# sband.net
KiCad netlist of a schematic drawn in Altium Designer
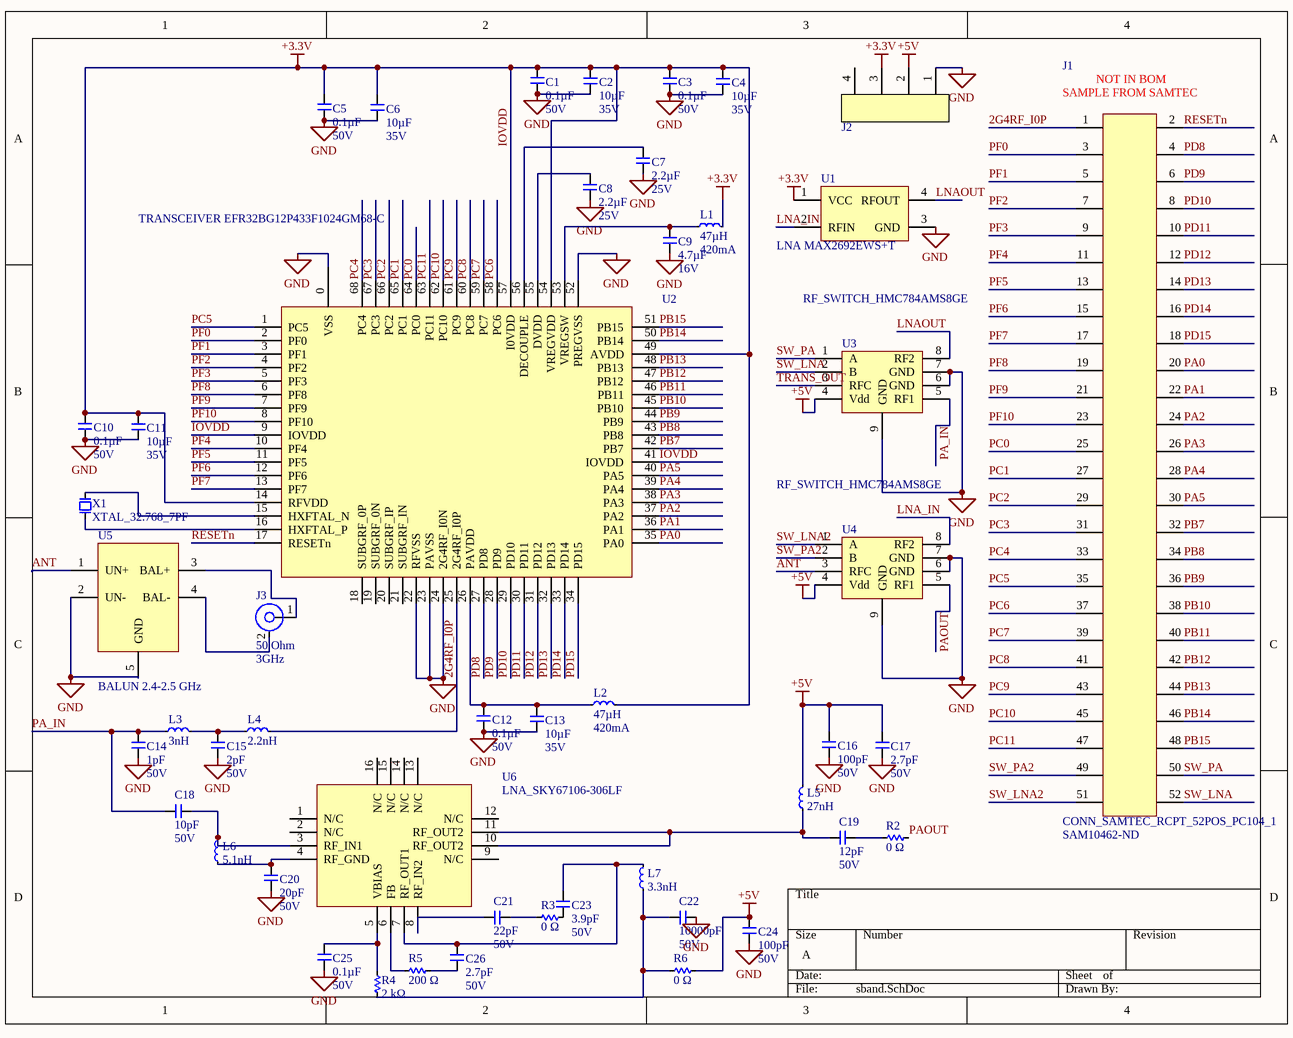
[diagram p0: sband.SchDoc]

(export (version "E")
  (design (tool "Eeschema 10.0.6"))
  (components
    (comp (ref "C1")
      (value "__template_cap")
      (footprint "C0603")
      (description "CAP CER 0603 0.1µF X7R 50V 10%")
      (fields
        (field (name "CAPACITANCE (SHORTHAND)") "0.1µF")
        (field (name "RATED VOLTAGE") "50V")
        (field (name "MANUFACTURER") "Murata Electronics North America")
      )
      (libsource (lib "passives") (part "__template_cap"))
    )
    (comp (ref "C2")
      (value "__template_cap")
      (footprint "C0603")
      (description "CAP CER 10UF 35V X5R 0603 20%")
      (fields
        (field (name "CAPACITANCE (SHORTHAND)") "10µF")
        (field (name "RATED VOLTAGE") "35V")
        (field (name "MANUFACTURER") "Murata Electronics North America")
      )
      (libsource (lib "passives") (part "__template_cap"))
    )
    (comp (ref "C3")
      (value "__template_cap")
      (footprint "C0603")
      (description "CAP CER 0603 0.1µF X7R 50V 10%")
      (fields
        (field (name "CAPACITANCE (SHORTHAND)") "0.1µF")
        (field (name "RATED VOLTAGE") "50V")
        (field (name "MANUFACTURER") "Murata Electronics North America")
      )
      (libsource (lib "passives") (part "__template_cap"))
    )
    (comp (ref "C4")
      (value "__template_cap")
      (footprint "C0603")
      (description "CAP CER 10UF 35V X5R 0603 20%")
      (fields
        (field (name "CAPACITANCE (SHORTHAND)") "10µF")
        (field (name "RATED VOLTAGE") "35V")
        (field (name "MANUFACTURER") "Murata Electronics North America")
      )
      (libsource (lib "passives") (part "__template_cap"))
    )
    (comp (ref "C5")
      (value "__template_cap")
      (footprint "C0603")
      (description "CAP CER 0603 0.1µF X7R 50V 10%")
      (fields
        (field (name "CAPACITANCE (SHORTHAND)") "0.1µF")
        (field (name "RATED VOLTAGE") "50V")
        (field (name "MANUFACTURER") "Murata Electronics North America")
      )
      (libsource (lib "passives") (part "__template_cap"))
    )
    (comp (ref "C6")
      (value "__template_cap")
      (footprint "C0603")
      (description "CAP CER 10UF 35V X5R 0603 20%")
      (fields
        (field (name "CAPACITANCE (SHORTHAND)") "10µF")
        (field (name "RATED VOLTAGE") "35V")
        (field (name "MANUFACTURER") "Murata Electronics North America")
      )
      (libsource (lib "passives") (part "__template_cap"))
    )
    (comp (ref "C7")
      (value "__template_cap")
      (footprint "C0603")
      (description "CAP CER 2.2UF 16V X5R 0603 10%")
      (fields
        (field (name "CAPACITANCE (SHORTHAND)") "2.2µF")
        (field (name "RATED VOLTAGE") "25V")
        (field (name "MANUFACTURER") "Murata Electronics North America")
      )
      (libsource (lib "passives") (part "__template_cap"))
    )
    (comp (ref "C8")
      (value "__template_cap")
      (footprint "C0603")
      (description "CAP CER 2.2UF 16V X5R 0603 10%")
      (fields
        (field (name "CAPACITANCE (SHORTHAND)") "2.2µF")
        (field (name "RATED VOLTAGE") "25V")
        (field (name "MANUFACTURER") "Murata Electronics North America")
      )
      (libsource (lib "passives") (part "__template_cap"))
    )
    (comp (ref "C9")
      (value "__template_cap")
      (footprint "C0603")
      (description "CAP CER 4.7UF 16V X5R 0603 10%")
      (fields
        (field (name "CAPACITANCE (SHORTHAND)") "4.7µF")
        (field (name "RATED VOLTAGE") "16V")
        (field (name "MANUFACTURER") "Yageo")
      )
      (libsource (lib "passives") (part "__template_cap"))
    )
    (comp (ref "C10")
      (value "__template_cap")
      (footprint "C0603")
      (description "CAP CER 0603 0.1µF X7R 50V 10%")
      (fields
        (field (name "CAPACITANCE (SHORTHAND)") "0.1µF")
        (field (name "RATED VOLTAGE") "50V")
        (field (name "MANUFACTURER") "Murata Electronics North America")
      )
      (libsource (lib "passives") (part "__template_cap"))
    )
    (comp (ref "C11")
      (value "__template_cap")
      (footprint "C0603")
      (description "CAP CER 10UF 35V X5R 0603 20%")
      (fields
        (field (name "CAPACITANCE (SHORTHAND)") "10µF")
        (field (name "RATED VOLTAGE") "35V")
        (field (name "MANUFACTURER") "Murata Electronics North America")
      )
      (libsource (lib "passives") (part "__template_cap"))
    )
    (comp (ref "C12")
      (value "__template_cap")
      (footprint "C0603")
      (description "CAP CER 0603 0.1µF X7R 50V 10%")
      (fields
        (field (name "CAPACITANCE (SHORTHAND)") "0.1µF")
        (field (name "RATED VOLTAGE") "50V")
        (field (name "MANUFACTURER") "Murata Electronics North America")
      )
      (libsource (lib "passives") (part "__template_cap"))
    )
    (comp (ref "C13")
      (value "__template_cap")
      (footprint "C0603")
      (description "CAP CER 10UF 35V X5R 0603 20%")
      (fields
        (field (name "CAPACITANCE (SHORTHAND)") "10µF")
        (field (name "RATED VOLTAGE") "35V")
        (field (name "MANUFACTURER") "Murata Electronics North America")
      )
      (libsource (lib "passives") (part "__template_cap"))
    )
    (comp (ref "C14")
      (value "__template_cap")
      (footprint "C0402")
      (description "CAP CER 1PF 50V C0G/NP0 0402")
      (fields
        (field (name "CAPACITANCE (SHORTHAND)") "1pF")
        (field (name "RATED VOLTAGE") "50V")
        (field (name "MANUFACTURER") "Murata Electronics North America")
        (field (name "TOLERANCE") "±0.1pF")
      )
      (libsource (lib "passives") (part "__template_cap"))
    )
    (comp (ref "C15")
      (value "__template_cap")
      (footprint "C0402")
      (description "CAP CER 2PF 50V C0G/NP0 0402")
      (fields
        (field (name "CAPACITANCE (SHORTHAND)") "2pF")
        (field (name "RATED VOLTAGE") "50V")
        (field (name "MANUFACTURER") "Murata Electronics North America")
        (field (name "TOLERANCE") "±0.1pF")
      )
      (libsource (lib "passives") (part "__template_cap"))
    )
    (comp (ref "C16")
      (value "__template_cap")
      (footprint "C0603")
      (description "CAP CER 100PF 50V C0G/NP0 0603")
      (fields
        (field (name "CAPACITANCE (SHORTHAND)") "100pF")
        (field (name "RATED VOLTAGE") "50V")
        (field (name "MANUFACTURER") "Murata Electronics North America")
      )
      (libsource (lib "passives") (part "__template_cap"))
    )
    (comp (ref "C17")
      (value "__template_cap")
      (footprint "C0402")
      (description "CAP CER 2.7PF 50V C0G/NP0 0402")
      (fields
        (field (name "CAPACITANCE (SHORTHAND)") "2.7pF")
        (field (name "RATED VOLTAGE") "50V")
        (field (name "MANUFACTURER") "Murata Electronics North America")
        (field (name "TOLERANCE") "±0.1pF")
      )
      (libsource (lib "passives") (part "__template_cap"))
    )
    (comp (ref "C18")
      (value "__template_cap")
      (footprint "C0402")
      (description "CAP CER 10PF 50V C0G/NP0 0402")
      (fields
        (field (name "CAPACITANCE (SHORTHAND)") "10pF")
        (field (name "RATED VOLTAGE") "50V")
        (field (name "MANUFACTURER") "Murata Electronics North America")
        (field (name "TOLERANCE") "±1%")
      )
      (libsource (lib "passives") (part "__template_cap"))
    )
    (comp (ref "C19")
      (value "__template_cap")
      (footprint "C0603")
      (description "CAP CER 12PF 50V C0G/NP0 0603")
      (fields
        (field (name "CAPACITANCE (SHORTHAND)") "12pF")
        (field (name "RATED VOLTAGE") "50V")
        (field (name "MANUFACTURER") "Murata Electronics North America")
      )
      (libsource (lib "passives") (part "__template_cap"))
    )
    (comp (ref "C20")
      (value "__template_cap")
      (footprint "C0402")
      (description "CAP CER 20PF 50V C0G/NP0 0402")
      (fields
        (field (name "CAPACITANCE (SHORTHAND)") "20pF")
        (field (name "RATED VOLTAGE") "50V")
        (field (name "MANUFACTURER") "Murata Electronics North America")
        (field (name "TOLERANCE") "±2%")
      )
      (libsource (lib "passives") (part "__template_cap"))
    )
    (comp (ref "C21")
      (value "__template_cap")
      (footprint "C0603")
      (description "CAP CER 22PF 50V C0G/NP0 0603")
      (fields
        (field (name "CAPACITANCE (SHORTHAND)") "22pF")
        (field (name "RATED VOLTAGE") "50V")
        (field (name "MANUFACTURER") "Murata Electronics North America")
      )
      (libsource (lib "passives") (part "__template_cap"))
    )
    (comp (ref "C22")
      (value "__template_cap")
      (footprint "C0603")
      (description "CAP CER 0603 10000pF X7R 50V 10%")
      (fields
        (field (name "CAPACITANCE (SHORTHAND)") "10000pF")
        (field (name "RATED VOLTAGE") "50V")
        (field (name "MANUFACTURER") "Murata Electronics North America")
      )
      (libsource (lib "passives") (part "__template_cap"))
    )
    (comp (ref "C23")
      (value "__template_cap")
      (footprint "C0402")
      (description "CAP CER 3.9PF 50V C0G/NP0 0402")
      (fields
        (field (name "CAPACITANCE (SHORTHAND)") "3.9pF")
        (field (name "RATED VOLTAGE") "50V")
        (field (name "MANUFACTURER") "Murata Electronics North America")
        (field (name "TOLERANCE") "±0.1pF")
      )
      (libsource (lib "passives") (part "__template_cap"))
    )
    (comp (ref "C24")
      (value "__template_cap")
      (footprint "C0603")
      (description "CAP CER 100PF 50V C0G/NP0 0603")
      (fields
        (field (name "CAPACITANCE (SHORTHAND)") "100pF")
        (field (name "RATED VOLTAGE") "50V")
        (field (name "MANUFACTURER") "Murata Electronics North America")
      )
      (libsource (lib "passives") (part "__template_cap"))
    )
    (comp (ref "C25")
      (value "__template_cap")
      (footprint "C0603")
      (description "CAP CER 0603 0.1µF X7R 50V 10%")
      (fields
        (field (name "CAPACITANCE (SHORTHAND)") "0.1µF")
        (field (name "RATED VOLTAGE") "50V")
        (field (name "MANUFACTURER") "Murata Electronics North America")
      )
      (libsource (lib "passives") (part "__template_cap"))
    )
    (comp (ref "C26")
      (value "__template_cap")
      (footprint "C0402")
      (description "CAP CER 2.7PF 50V C0G/NP0 0402")
      (fields
        (field (name "CAPACITANCE (SHORTHAND)") "2.7pF")
        (field (name "RATED VOLTAGE") "50V")
        (field (name "MANUFACTURER") "Murata Electronics North America")
        (field (name "TOLERANCE") "±0.1pF")
      )
      (libsource (lib "passives") (part "__template_cap"))
    )
    (comp (ref "J1")
      (value "CONN_SAMTEC_RCPT_52POS_PC104_1")
      (footprint "SAMTEC_ESQ-126-39-G-D")
      (description "CONN RCPT 52POS .100\" DUAL GOLD")
      (fields
        (field (name "MANUFACTURER") "Samtec Inc.")
        (field (name "MANUFACTURER PART NUMBER") "ESQ-126-39-G-D")
        (field (name "SUPPLIER PART NUMBER 1") "SAM10462-ND")
      )
      (libsource (lib "connector") (part "CONN_SAMTEC_RCPT_52POS_PC104_1"))
    )
    (comp (ref "J2")
      (value "CONN_1x4_MALE_SMD")
      (footprint "CONN_1x4_100MIL_MALE_SMD")
      (description "CONN HEADER 4POS MALE SMD")
      (fields
        (field (name "MANUFACTURER") "3M")
        (field (name "MANUFACTURER PART NUMBER") "961104-6700-AR-TP")
      )
      (libsource (lib "Stanford Student Space Initiative") (part "Symbol"))
    )
    (comp (ref "J3")
      (value "CONN_SMA_JACK_R/A_50_OHM_PCB")
      (footprint "TE_SMA_JACK_RA_5-1814400-1")
      (description "CONN SMA JACK R/A 50 OHM PCB")
      (fields
        (field (name "IMPEDANCE") "50 Ohm")
        (field (name "FREQUENCY - MAX") "3GHz")
        (field (name "MANUFACTURER") "TE Connectivity")
        (field (name "MANUFACTURER PART NUMBER") "5-1814400-1")
      )
      (libsource (lib "Stanford Student Space Initiative") (part "CONN_SMA_JACK_R/A_50_OHM_PCB"))
    )
    (comp (ref "L1")
      (value "INDUCTOR 47UH 420MA 1210 SMD")
      (footprint "C1210")
      (fields
        (field (name "MANUFACTURER") "Taiyo Yuden")
        (field (name "MANUFACTURER PART NUMBER") "BRL3225T470K")
        (field (name "TOLERANCE") "±10%")
        (field (name "INDUCTANCE") "47µH")
        (field (name "CURRENT - SATURATION") "420mA")
      )
      (libsource (lib "inductor") (part "IND_BRL3225T470K"))
    )
    (comp (ref "L2")
      (value "INDUCTOR 47UH 420MA 1210 SMD")
      (footprint "C1210")
      (fields
        (field (name "MANUFACTURER") "Taiyo Yuden")
        (field (name "MANUFACTURER PART NUMBER") "BRL3225T470K")
        (field (name "TOLERANCE") "±10%")
        (field (name "INDUCTANCE") "47µH")
        (field (name "CURRENT - SATURATION") "420mA")
      )
      (libsource (lib "inductor") (part "IND_BRL3225T470K"))
    )
    (comp (ref "L3")
      (value "__template_inductor")
      (footprint "R0402")
      (description "FIXED IND 3NH 1.35A 63 MOHM SMD")
      (fields
        (field (name "INDUCTANCE") "3nH")
        (field (name "MANUFACTURER") "Murata Electronics North America")
      )
      (libsource (lib "passives") (part "__template_inductor"))
    )
    (comp (ref "L4")
      (value "__template_inductor")
      (footprint "R0402")
      (description "FIXED IND 2.2NH 2.53A 22 MOHM")
      (fields
        (field (name "INDUCTANCE") "2.2nH")
        (field (name "MANUFACTURER") "Murata Electronics North America")
      )
      (libsource (lib "passives") (part "__template_inductor"))
    )
    (comp (ref "L5")
      (value "__template_inductor")
      (footprint "R0402")
      (description "FIXED IND 27NH 680MA 288 MOHM")
      (fields
        (field (name "INDUCTANCE") "27nH")
        (field (name "MANUFACTURER") "Murata Electronics North America")
      )
      (libsource (lib "passives") (part "__template_inductor"))
    )
    (comp (ref "L6")
      (value "__template_inductor")
      (footprint "R0402")
      (description "FIXED IND 5.1NH 1.77A 40 MOHM")
      (fields
        (field (name "INDUCTANCE") "5.1nH")
        (field (name "MANUFACTURER") "Murata Electronics North America")
      )
      (libsource (lib "passives") (part "__template_inductor"))
    )
    (comp (ref "L7")
      (value "__template_inductor")
      (footprint "R0402")
      (description "FIXED IND 3.3NH 2A 30 MOHM SMD")
      (fields
        (field (name "INDUCTANCE") "3.3nH")
        (field (name "MANUFACTURER") "Murata Electronics North America")
      )
      (libsource (lib "passives") (part "__template_inductor"))
    )
    (comp (ref "R2")
      (value "__template_resistor")
      (footprint "R0603")
      (description "RES SMD 0 OHM JUMPER 1/10W 0603")
      (fields
        (field (name "RESISTANCE") "0 Ω")
        (field (name "MANUFACTURER PART NUMBER") "RC0603FR-070RL")
        (field (name "MANUFACTURER") "Yageo")
      )
      (libsource (lib "passives") (part "__template_resistor"))
    )
    (comp (ref "R3")
      (value "__template_resistor")
      (footprint "R0603")
      (description "RES SMD 0 OHM JUMPER 1/10W 0603")
      (fields
        (field (name "RESISTANCE") "0 Ω")
        (field (name "MANUFACTURER PART NUMBER") "RC0603FR-070RL")
        (field (name "MANUFACTURER") "Yageo")
      )
      (libsource (lib "passives") (part "__template_resistor"))
    )
    (comp (ref "R4")
      (value "__template_resistor")
      (footprint "R0603")
      (description "RES SMD 2K OHM 1% 1/10W 0603")
      (fields
        (field (name "RESISTANCE") "2 kΩ")
        (field (name "MANUFACTURER PART NUMBER") "RC0603FR-072KL")
        (field (name "MANUFACTURER") "Yageo")
      )
      (libsource (lib "passives") (part "__template_resistor"))
    )
    (comp (ref "R5")
      (value "__template_resistor")
      (footprint "R0603")
      (description "RES SMD 200 OHM 1% 1/10W 0603")
      (fields
        (field (name "RESISTANCE") "200 Ω")
        (field (name "MANUFACTURER PART NUMBER") "RC0603FR-07200RL")
        (field (name "MANUFACTURER") "Yageo")
      )
      (libsource (lib "passives") (part "__template_resistor"))
    )
    (comp (ref "R6")
      (value "__template_resistor")
      (footprint "R0603")
      (description "RES SMD 0 OHM JUMPER 1/10W 0603")
      (fields
        (field (name "RESISTANCE") "0 Ω")
        (field (name "MANUFACTURER PART NUMBER") "RC0603FR-070RL")
        (field (name "MANUFACTURER") "Yageo")
      )
      (libsource (lib "passives") (part "__template_resistor"))
    )
    (comp (ref "U1")
      (value "LNA MAX2692EWS+T")
      (footprint "4WLP")
      (libsource (lib "rf") (part "LNA MAX2692EWS+T"))
    )
    (comp (ref "U2")
      (value "TRANSCEIVER EFR32BG12P433F1024GM68-C")
      (footprint "68QFN")
      (libsource (lib "rf") (part "TRANSCEIVER EFR32BG12P433F1024GM68-C"))
    )
    (comp (ref "U3")
      (value "RF_SWITCH_HMC784AMS8GE")
      (footprint "8MSOP65E")
      (libsource (lib "rf") (part "RF_SWITCH_HMC784AMS8GE"))
    )
    (comp (ref "U4")
      (value "RF_SWITCH_HMC784AMS8GE")
      (footprint "8MSOP65E")
      (libsource (lib "rf") (part "RF_SWITCH_HMC784AMS8GE"))
    )
    (comp (ref "U5")
      (value "BALUN 2.4-2.5 GHz")
      (footprint "2450BL15B200")
      (fields
        (field (name "MANUFACTURER") "Johanson")
        (field (name "MANUFACTURER PART NUMBER") "2450BL15B200E")
      )
      (libsource (lib "rf") (part "BALUN_2450BL15B200E"))
    )
    (comp (ref "U6")
      (value "LNA_SKY67106-306LF")
      (footprint "16QFN")
      (description "TWO-STAGE LNA")
      (libsource (lib "rf") (part "LNA_SKY67106-306LF"))
    )
    (comp (ref "X1")
      (value "XTAL_32.768_7PF")
      (footprint "XTAL_ECS-0.327-7-34B-TR")
      (description "CRYSTAL 32.7680KHZ 7PF SMD")
      (fields
        (field (name "MANUFACTURER") "ECS International")
        (field (name "MANUFACTURER PART NUMBER") "ECS-.327-7-34B-TR")
      )
      (libsource (lib "oscillator") (part "XTAL_32.768_7PF"))
    )
  )
  (nets
    (net (code "1") (name "+3.3V") (class "Default")
      (node (ref "C1") (pin "1") (pintype "passive"))
      (node (ref "C10") (pin "1") (pintype "passive"))
      (node (ref "C11") (pin "1") (pintype "passive"))
      (node (ref "C2") (pin "1") (pintype "passive"))
      (node (ref "C3") (pin "1") (pintype "passive"))
      (node (ref "C4") (pin "1") (pintype "passive"))
      (node (ref "C5") (pin "1") (pintype "passive"))
      (node (ref "C6") (pin "1") (pintype "passive"))
      (node (ref "J2") (pin "3") (pinfunction "3_3") (pintype "passive"))
      (node (ref "L1") (pin "1") (pintype "passive"))
      (node (ref "L2") (pin "1") (pintype "passive"))
      (node (ref "U1") (pin "1") (pinfunction "VCC_1") (pintype "passive"))
      (node (ref "U2") (pin "14") (pinfunction "RFVDD_14") (pintype "passive"))
      (node (ref "U2") (pin "41") (pinfunction "IOVDD_41") (pintype "passive"))
      (node (ref "U2") (pin "49") (pinfunction "AVDD_49") (pintype "passive"))
      (node (ref "U2") (pin "54") (pinfunction "VREGVDD_54") (pintype "passive"))
      (node (ref "U2") (pin "57") (pinfunction "I0VDD_57") (pintype "passive"))
      (node (ref "U2") (pin "9") (pinfunction "IOVDD_9") (pintype "passive"))
    )
    (net (code "2") (name "+5V") (class "Default")
      (node (ref "C16") (pin "1") (pintype "passive"))
      (node (ref "C17") (pin "1") (pintype "passive"))
      (node (ref "C24") (pin "1") (pintype "passive"))
      (node (ref "J2") (pin "2") (pinfunction "2_2") (pintype "passive"))
      (node (ref "L5") (pin "2") (pintype "passive"))
      (node (ref "R6") (pin "2") (pintype "passive"))
      (node (ref "U3") (pin "4") (pinfunction "Vdd_4") (pintype "passive"))
      (node (ref "U4") (pin "4") (pinfunction "Vdd_4") (pintype "passive"))
    )
    (net (code "3") (name "/2G4RF_I0P") (class "Default")
      (node (ref "J1") (pin "1") (pinfunction "1_1") (pintype "passive"))
      (node (ref "L4") (pin "2") (pintype "passive"))
      (node (ref "U2") (pin "25") (pinfunction "2G4RF_I0P_25") (pintype "passive"))
    )
    (net (code "4") (name "/ANT") (class "Default")
      (node (ref "U4") (pin "3") (pinfunction "RFC_3") (pintype "passive"))
      (node (ref "U5") (pin "1") (pinfunction "UN+_1") (pintype "passive"))
    )
    (net (code "5") (name "/LNAOUT") (class "Default")
      (node (ref "U1") (pin "4") (pinfunction "RFOUT_4") (pintype "passive"))
      (node (ref "U3") (pin "8") (pinfunction "RF2_8") (pintype "passive"))
    )
    (net (code "6") (name "/LNA_IN") (class "Default")
      (node (ref "U1") (pin "2") (pinfunction "RFIN_2") (pintype "passive"))
      (node (ref "U4") (pin "8") (pinfunction "RF2_8") (pintype "passive"))
    )
    (net (code "7") (name "/PA0") (class "Default")
      (node (ref "J1") (pin "20") (pinfunction "20_20") (pintype "passive"))
      (node (ref "U2") (pin "35") (pinfunction "PA0_35") (pintype "passive"))
    )
    (net (code "8") (name "/PA1") (class "Default")
      (node (ref "J1") (pin "22") (pinfunction "22_22") (pintype "passive"))
      (node (ref "U2") (pin "36") (pinfunction "PA1_36") (pintype "passive"))
    )
    (net (code "9") (name "/PA2") (class "Default")
      (node (ref "J1") (pin "24") (pinfunction "24_24") (pintype "passive"))
      (node (ref "U2") (pin "37") (pinfunction "PA2_37") (pintype "passive"))
    )
    (net (code "10") (name "/PA3") (class "Default")
      (node (ref "J1") (pin "26") (pinfunction "26_26") (pintype "passive"))
      (node (ref "U2") (pin "38") (pinfunction "PA3_38") (pintype "passive"))
    )
    (net (code "11") (name "/PA4") (class "Default")
      (node (ref "J1") (pin "28") (pinfunction "28_28") (pintype "passive"))
      (node (ref "U2") (pin "39") (pinfunction "PA4_39") (pintype "passive"))
    )
    (net (code "12") (name "/PA5") (class "Default")
      (node (ref "J1") (pin "30") (pinfunction "30_30") (pintype "passive"))
      (node (ref "U2") (pin "40") (pinfunction "PA5_40") (pintype "passive"))
    )
    (net (code "13") (name "/PAOUT") (class "Default")
      (node (ref "R2") (pin "2") (pintype "passive"))
      (node (ref "U4") (pin "5") (pinfunction "RF1_5") (pintype "passive"))
    )
    (net (code "14") (name "/PA_IN") (class "Default")
      (node (ref "C14") (pin "1") (pintype "passive"))
      (node (ref "C18") (pin "1") (pintype "passive"))
      (node (ref "L3") (pin "1") (pintype "passive"))
      (node (ref "U3") (pin "5") (pinfunction "RF1_5") (pintype "passive"))
    )
    (net (code "15") (name "/PB7") (class "Default")
      (node (ref "J1") (pin "32") (pinfunction "32_32") (pintype "passive"))
      (node (ref "U2") (pin "42") (pinfunction "PB7_42") (pintype "passive"))
    )
    (net (code "16") (name "/PB8") (class "Default")
      (node (ref "J1") (pin "34") (pinfunction "34_34") (pintype "passive"))
      (node (ref "U2") (pin "43") (pinfunction "PB8_43") (pintype "passive"))
    )
    (net (code "17") (name "/PB9") (class "Default")
      (node (ref "J1") (pin "36") (pinfunction "36_36") (pintype "passive"))
      (node (ref "U2") (pin "44") (pinfunction "PB9_44") (pintype "passive"))
    )
    (net (code "18") (name "/PB10") (class "Default")
      (node (ref "J1") (pin "38") (pinfunction "38_38") (pintype "passive"))
      (node (ref "U2") (pin "45") (pinfunction "PB10_45") (pintype "passive"))
    )
    (net (code "19") (name "/PB11") (class "Default")
      (node (ref "J1") (pin "40") (pinfunction "40_40") (pintype "passive"))
      (node (ref "U2") (pin "46") (pinfunction "PB11_46") (pintype "passive"))
    )
    (net (code "20") (name "/PB12") (class "Default")
      (node (ref "J1") (pin "42") (pinfunction "42_42") (pintype "passive"))
      (node (ref "U2") (pin "47") (pinfunction "PB12_47") (pintype "passive"))
    )
    (net (code "21") (name "/PB13") (class "Default")
      (node (ref "J1") (pin "44") (pinfunction "44_44") (pintype "passive"))
      (node (ref "U2") (pin "48") (pinfunction "PB13_48") (pintype "passive"))
    )
    (net (code "22") (name "/PB14") (class "Default")
      (node (ref "J1") (pin "46") (pinfunction "46_46") (pintype "passive"))
      (node (ref "U2") (pin "50") (pinfunction "PB14_50") (pintype "passive"))
    )
    (net (code "23") (name "/PB15") (class "Default")
      (node (ref "J1") (pin "48") (pinfunction "48_48") (pintype "passive"))
      (node (ref "U2") (pin "51") (pinfunction "PB15_51") (pintype "passive"))
    )
    (net (code "24") (name "/PC0") (class "Default")
      (node (ref "J1") (pin "25") (pinfunction "25_25") (pintype "passive"))
      (node (ref "U2") (pin "64") (pinfunction "PC0_64") (pintype "passive"))
    )
    (net (code "25") (name "/PC1") (class "Default")
      (node (ref "J1") (pin "27") (pinfunction "27_27") (pintype "passive"))
      (node (ref "U2") (pin "65") (pinfunction "PC1_65") (pintype "passive"))
    )
    (net (code "26") (name "/PC2") (class "Default")
      (node (ref "J1") (pin "29") (pinfunction "29_29") (pintype "passive"))
      (node (ref "U2") (pin "66") (pinfunction "PC2_66") (pintype "passive"))
    )
    (net (code "27") (name "/PC3") (class "Default")
      (node (ref "J1") (pin "31") (pinfunction "31_31") (pintype "passive"))
      (node (ref "U2") (pin "67") (pinfunction "PC3_67") (pintype "passive"))
    )
    (net (code "28") (name "/PC4") (class "Default")
      (node (ref "J1") (pin "33") (pinfunction "33_33") (pintype "passive"))
      (node (ref "U2") (pin "68") (pinfunction "PC4_68") (pintype "passive"))
    )
    (net (code "29") (name "/PC5") (class "Default")
      (node (ref "J1") (pin "35") (pinfunction "35_35") (pintype "passive"))
      (node (ref "U2") (pin "1") (pinfunction "PC5_1") (pintype "passive"))
    )
    (net (code "30") (name "/PC6") (class "Default")
      (node (ref "J1") (pin "37") (pinfunction "37_37") (pintype "passive"))
      (node (ref "U2") (pin "58") (pinfunction "PC6_58") (pintype "passive"))
    )
    (net (code "31") (name "/PC7") (class "Default")
      (node (ref "J1") (pin "39") (pinfunction "39_39") (pintype "passive"))
      (node (ref "U2") (pin "59") (pinfunction "PC7_59") (pintype "passive"))
    )
    (net (code "32") (name "/PC8") (class "Default")
      (node (ref "J1") (pin "41") (pinfunction "41_41") (pintype "passive"))
      (node (ref "U2") (pin "60") (pinfunction "PC8_60") (pintype "passive"))
    )
    (net (code "33") (name "/PC9") (class "Default")
      (node (ref "J1") (pin "43") (pinfunction "43_43") (pintype "passive"))
      (node (ref "U2") (pin "61") (pinfunction "PC9_61") (pintype "passive"))
    )
    (net (code "34") (name "/PC10") (class "Default")
      (node (ref "J1") (pin "45") (pinfunction "45_45") (pintype "passive"))
      (node (ref "U2") (pin "62") (pinfunction "PC10_62") (pintype "passive"))
    )
    (net (code "35") (name "/PC11") (class "Default")
      (node (ref "J1") (pin "47") (pinfunction "47_47") (pintype "passive"))
      (node (ref "U2") (pin "63") (pinfunction "PC11_63") (pintype "passive"))
    )
    (net (code "36") (name "/PD8") (class "Default")
      (node (ref "J1") (pin "4") (pinfunction "4_4") (pintype "passive"))
      (node (ref "U2") (pin "27") (pinfunction "PD8_27") (pintype "passive"))
    )
    (net (code "37") (name "/PD9") (class "Default")
      (node (ref "J1") (pin "6") (pinfunction "6_6") (pintype "passive"))
      (node (ref "U2") (pin "28") (pinfunction "PD9_28") (pintype "passive"))
    )
    (net (code "38") (name "/PD10") (class "Default")
      (node (ref "J1") (pin "8") (pinfunction "8_8") (pintype "passive"))
      (node (ref "U2") (pin "29") (pinfunction "PD10_29") (pintype "passive"))
    )
    (net (code "39") (name "/PD11") (class "Default")
      (node (ref "J1") (pin "10") (pinfunction "10_10") (pintype "passive"))
      (node (ref "U2") (pin "30") (pinfunction "PD11_30") (pintype "passive"))
    )
    (net (code "40") (name "/PD12") (class "Default")
      (node (ref "J1") (pin "12") (pinfunction "12_12") (pintype "passive"))
      (node (ref "U2") (pin "31") (pinfunction "PD12_31") (pintype "passive"))
    )
    (net (code "41") (name "/PD13") (class "Default")
      (node (ref "J1") (pin "14") (pinfunction "14_14") (pintype "passive"))
      (node (ref "U2") (pin "32") (pinfunction "PD13_32") (pintype "passive"))
    )
    (net (code "42") (name "/PD14") (class "Default")
      (node (ref "J1") (pin "16") (pinfunction "16_16") (pintype "passive"))
      (node (ref "U2") (pin "33") (pinfunction "PD14_33") (pintype "passive"))
    )
    (net (code "43") (name "/PD15") (class "Default")
      (node (ref "J1") (pin "18") (pinfunction "18_18") (pintype "passive"))
      (node (ref "U2") (pin "34") (pinfunction "PD15_34") (pintype "passive"))
    )
    (net (code "44") (name "/PF0") (class "Default")
      (node (ref "J1") (pin "3") (pinfunction "3_3") (pintype "passive"))
      (node (ref "U2") (pin "2") (pinfunction "PF0_2") (pintype "passive"))
    )
    (net (code "45") (name "/PF1") (class "Default")
      (node (ref "J1") (pin "5") (pinfunction "5_5") (pintype "passive"))
      (node (ref "U2") (pin "3") (pinfunction "PF1_3") (pintype "passive"))
    )
    (net (code "46") (name "/PF2") (class "Default")
      (node (ref "J1") (pin "7") (pinfunction "7_7") (pintype "passive"))
      (node (ref "U2") (pin "4") (pinfunction "PF2_4") (pintype "passive"))
    )
    (net (code "47") (name "/PF3") (class "Default")
      (node (ref "J1") (pin "9") (pinfunction "9_9") (pintype "passive"))
      (node (ref "U2") (pin "5") (pinfunction "PF3_5") (pintype "passive"))
    )
    (net (code "48") (name "/PF4") (class "Default")
      (node (ref "J1") (pin "11") (pinfunction "11_11") (pintype "passive"))
      (node (ref "U2") (pin "10") (pinfunction "PF4_10") (pintype "passive"))
    )
    (net (code "49") (name "/PF5") (class "Default")
      (node (ref "J1") (pin "13") (pinfunction "13_13") (pintype "passive"))
      (node (ref "U2") (pin "11") (pinfunction "PF5_11") (pintype "passive"))
    )
    (net (code "50") (name "/PF6") (class "Default")
      (node (ref "J1") (pin "15") (pinfunction "15_15") (pintype "passive"))
      (node (ref "U2") (pin "12") (pinfunction "PF6_12") (pintype "passive"))
    )
    (net (code "51") (name "/PF7") (class "Default")
      (node (ref "J1") (pin "17") (pinfunction "17_17") (pintype "passive"))
      (node (ref "U2") (pin "13") (pinfunction "PF7_13") (pintype "passive"))
    )
    (net (code "52") (name "/PF8") (class "Default")
      (node (ref "J1") (pin "19") (pinfunction "19_19") (pintype "passive"))
      (node (ref "U2") (pin "6") (pinfunction "PF8_6") (pintype "passive"))
    )
    (net (code "53") (name "/PF9") (class "Default")
      (node (ref "J1") (pin "21") (pinfunction "21_21") (pintype "passive"))
      (node (ref "U2") (pin "7") (pinfunction "PF9_7") (pintype "passive"))
    )
    (net (code "54") (name "/PF10") (class "Default")
      (node (ref "J1") (pin "23") (pinfunction "23_23") (pintype "passive"))
      (node (ref "U2") (pin "8") (pinfunction "PF10_8") (pintype "passive"))
    )
    (net (code "55") (name "/RESETn") (class "Default")
      (node (ref "J1") (pin "2") (pinfunction "2_2") (pintype "passive"))
      (node (ref "U2") (pin "17") (pinfunction "RESETn_17") (pintype "passive"))
    )
    (net (code "56") (name "/SW_LNA") (class "Default")
      (node (ref "J1") (pin "52") (pinfunction "52_52") (pintype "passive"))
      (node (ref "U3") (pin "2") (pinfunction "B_2") (pintype "passive"))
    )
    (net (code "57") (name "/SW_LNA2") (class "Default")
      (node (ref "J1") (pin "51") (pinfunction "51_51") (pintype "passive"))
      (node (ref "U4") (pin "1") (pinfunction "A_1") (pintype "passive"))
    )
    (net (code "58") (name "/SW_PA") (class "Default")
      (node (ref "J1") (pin "50") (pinfunction "50_50") (pintype "passive"))
      (node (ref "U3") (pin "1") (pinfunction "A_1") (pintype "passive"))
    )
    (net (code "59") (name "/SW_PA2") (class "Default")
      (node (ref "J1") (pin "49") (pinfunction "49_49") (pintype "passive"))
      (node (ref "U4") (pin "2") (pinfunction "B_2") (pintype "passive"))
    )
    (net (code "60") (name "/TRANS_OUT") (class "Default")
      (node (ref "U3") (pin "3") (pinfunction "RFC_3") (pintype "passive"))
    )
    (net (code "61") (name "GND") (class "Default")
      (node (ref "C1") (pin "2") (pintype "passive"))
      (node (ref "C10") (pin "2") (pintype "passive"))
      (node (ref "C11") (pin "2") (pintype "passive"))
      (node (ref "C12") (pin "2") (pintype "passive"))
      (node (ref "C13") (pin "2") (pintype "passive"))
      (node (ref "C14") (pin "2") (pintype "passive"))
      (node (ref "C15") (pin "2") (pintype "passive"))
      (node (ref "C16") (pin "2") (pintype "passive"))
      (node (ref "C17") (pin "2") (pintype "passive"))
      (node (ref "C2") (pin "2") (pintype "passive"))
      (node (ref "C20") (pin "2") (pintype "passive"))
      (node (ref "C22") (pin "2") (pintype "passive"))
      (node (ref "C24") (pin "2") (pintype "passive"))
      (node (ref "C25") (pin "2") (pintype "passive"))
      (node (ref "C3") (pin "2") (pintype "passive"))
      (node (ref "C4") (pin "2") (pintype "passive"))
      (node (ref "C5") (pin "2") (pintype "passive"))
      (node (ref "C6") (pin "2") (pintype "passive"))
      (node (ref "C7") (pin "2") (pintype "passive"))
      (node (ref "C8") (pin "2") (pintype "passive"))
      (node (ref "C9") (pin "2") (pintype "passive"))
      (node (ref "J2") (pin "1") (pinfunction "1_1") (pintype "passive"))
      (node (ref "U1") (pin "3") (pinfunction "GND_3") (pintype "passive"))
      (node (ref "U2") (pin "0") (pinfunction "VSS_0") (pintype "passive"))
      (node (ref "U2") (pin "22") (pinfunction "RFVSS_22") (pintype "passive"))
      (node (ref "U2") (pin "23") (pinfunction "PAVSS_23") (pintype "passive"))
      (node (ref "U2") (pin "24") (pinfunction "2G4RF_I0N_24") (pintype "passive"))
      (node (ref "U2") (pin "52") (pinfunction "PREGVSS_52") (pintype "passive"))
      (node (ref "U3") (pin "6") (pinfunction "GND_6") (pintype "passive"))
      (node (ref "U3") (pin "7") (pinfunction "GND_7") (pintype "passive"))
      (node (ref "U3") (pin "9") (pinfunction "GND_9") (pintype "passive"))
      (node (ref "U4") (pin "6") (pinfunction "GND_6") (pintype "passive"))
      (node (ref "U4") (pin "7") (pinfunction "GND_7") (pintype "passive"))
      (node (ref "U4") (pin "9") (pinfunction "GND_9") (pintype "passive"))
      (node (ref "U5") (pin "2") (pinfunction "UN-_2") (pintype "passive"))
      (node (ref "U5") (pin "5") (pinfunction "GND_5") (pintype "passive"))
    )
    (net (code "62") (name "Net-(C15-Pad1)") (class "Default")
      (node (ref "C15") (pin "1") (pintype "passive"))
      (node (ref "L3") (pin "2") (pintype "passive"))
      (node (ref "L4") (pin "1") (pintype "passive"))
    )
    (net (code "63") (name "Net-(C19-Pad1)") (class "Default")
      (node (ref "C19") (pin "1") (pintype "passive"))
      (node (ref "L5") (pin "1") (pintype "passive"))
      (node (ref "U6") (pin "10") (pinfunction "RF_OUT2_10") (pintype "passive"))
      (node (ref "U6") (pin "11") (pinfunction "RF_OUT2_11") (pintype "passive"))
    )
    (net (code "64") (name "Net-(C19-Pad2)") (class "Default")
      (node (ref "C19") (pin "2") (pintype "passive"))
      (node (ref "R2") (pin "1") (pintype "passive"))
    )
    (net (code "65") (name "Net-(C21-Pad2)") (class "Default")
      (node (ref "C21") (pin "2") (pintype "passive"))
      (node (ref "R3") (pin "1") (pintype "passive"))
    )
    (net (code "66") (name "Net-(C22-Pad1)") (class "Default")
      (node (ref "C22") (pin "1") (pintype "passive"))
      (node (ref "L7") (pin "1") (pintype "passive"))
      (node (ref "R4") (pin "1") (pintype "passive"))
      (node (ref "R6") (pin "1") (pintype "passive"))
    )
    (net (code "67") (name "Net-(C23-Pad1)") (class "Default")
      (node (ref "C23") (pin "1") (pintype "passive"))
      (node (ref "R3") (pin "2") (pintype "passive"))
    )
    (net (code "68") (name "Net-(C26-Pad2)") (class "Default")
      (node (ref "C26") (pin "2") (pintype "passive"))
      (node (ref "R5") (pin "2") (pintype "passive"))
    )
    (net (code "69") (name "Net-(U2-DECOUPLE)") (class "Default")
      (node (ref "C7") (pin "1") (pintype "passive"))
      (node (ref "U2") (pin "56") (pinfunction "DECOUPLE_56") (pintype "passive"))
    )
    (net (code "70") (name "Net-(U2-DVDD)") (class "Default")
      (node (ref "C8") (pin "1") (pintype "passive"))
      (node (ref "U2") (pin "55") (pinfunction "DVDD_55") (pintype "passive"))
    )
    (net (code "71") (name "Net-(U2-HXFTAL_N)") (class "Default")
      (node (ref "U2") (pin "15") (pinfunction "HXFTAL_N_15") (pintype "passive"))
      (node (ref "X1") (pin "1") (pinfunction "1_1") (pintype "passive"))
    )
    (net (code "72") (name "Net-(U2-HXFTAL_P)") (class "Default")
      (node (ref "U2") (pin "16") (pinfunction "HXFTAL_P_16") (pintype "passive"))
      (node (ref "X1") (pin "2") (pinfunction "2_2") (pintype "passive"))
    )
    (net (code "73") (name "Net-(U2-PAVDD)") (class "Default")
      (node (ref "C12") (pin "1") (pintype "passive"))
      (node (ref "C13") (pin "1") (pintype "passive"))
      (node (ref "L2") (pin "2") (pintype "passive"))
      (node (ref "U2") (pin "26") (pinfunction "PAVDD_26") (pintype "passive"))
    )
    (net (code "74") (name "Net-(U2-VREGSW)") (class "Default")
      (node (ref "C9") (pin "1") (pintype "passive"))
      (node (ref "L1") (pin "2") (pintype "passive"))
      (node (ref "U2") (pin "53") (pinfunction "VREGSW_53") (pintype "passive"))
    )
    (net (code "75") (name "Net-(U5-BAL+)") (class "Default")
      (node (ref "J3") (pin "1") (pinfunction "1_1") (pintype "passive"))
      (node (ref "U5") (pin "3") (pinfunction "BAL+_3") (pintype "passive"))
    )
    (net (code "76") (name "Net-(U5-BAL-)") (class "Default")
      (node (ref "J3") (pin "2") (pinfunction "2_2") (pintype "passive"))
      (node (ref "U5") (pin "4") (pinfunction "BAL-_4") (pintype "passive"))
    )
    (net (code "77") (name "Net-(U6-FB)") (class "Default")
      (node (ref "R5") (pin "1") (pintype "passive"))
      (node (ref "U6") (pin "6") (pinfunction "FB_6") (pintype "passive"))
    )
    (net (code "78") (name "Net-(U6-RF_GND)") (class "Default")
      (node (ref "C20") (pin "1") (pintype "passive"))
      (node (ref "L6") (pin "1") (pintype "passive"))
      (node (ref "U6") (pin "4") (pinfunction "RF_GND_4") (pintype "passive"))
    )
    (net (code "79") (name "Net-(U6-RF_IN1)") (class "Default")
      (node (ref "C18") (pin "2") (pintype "passive"))
      (node (ref "L6") (pin "2") (pintype "passive"))
      (node (ref "U6") (pin "3") (pinfunction "RF_IN1_3") (pintype "passive"))
    )
    (net (code "80") (name "Net-(U6-RF_IN2)") (class "Default")
      (node (ref "C21") (pin "1") (pintype "passive"))
      (node (ref "U6") (pin "8") (pinfunction "RF_IN2_8") (pintype "passive"))
    )
    (net (code "81") (name "Net-(U6-RF_OUT1)") (class "Default")
      (node (ref "C23") (pin "2") (pintype "passive"))
      (node (ref "C26") (pin "1") (pintype "passive"))
      (node (ref "L7") (pin "2") (pintype "passive"))
      (node (ref "U6") (pin "7") (pinfunction "RF_OUT1_7") (pintype "passive"))
    )
    (net (code "82") (name "Net-(U6-VBIAS)") (class "Default")
      (node (ref "C25") (pin "1") (pintype "passive"))
      (node (ref "R4") (pin "2") (pintype "passive"))
      (node (ref "U6") (pin "5") (pinfunction "VBIAS_5") (pintype "passive"))
    )
    (net (code "83") (name "unconnected-(J2-Pad4)") (class "Default")
      (node (ref "J2") (pin "4") (pinfunction "4_4") (pintype "passive"))
    )
    (net (code "84") (name "unconnected-(U2-SUBGRF_0N-Pad19)") (class "Default")
      (node (ref "U2") (pin "19") (pinfunction "SUBGRF_0N_19") (pintype "passive"))
    )
    (net (code "85") (name "unconnected-(U2-SUBGRF_0P-Pad18)") (class "Default")
      (node (ref "U2") (pin "18") (pinfunction "SUBGRF_0P_18") (pintype "passive"))
    )
    (net (code "86") (name "unconnected-(U2-SUBGRF_IN-Pad21)") (class "Default")
      (node (ref "U2") (pin "21") (pinfunction "SUBGRF_IN_21") (pintype "passive"))
    )
    (net (code "87") (name "unconnected-(U2-SUBGRF_IP-Pad20)") (class "Default")
      (node (ref "U2") (pin "20") (pinfunction "SUBGRF_IP_20") (pintype "passive"))
    )
    (net (code "88") (name "unconnected-(U6-N{slash}C-Pad1)") (class "Default")
      (node (ref "U6") (pin "1") (pinfunction "N/C_1") (pintype "passive"))
    )
    (net (code "89") (name "unconnected-(U6-N{slash}C-Pad2)") (class "Default")
      (node (ref "U6") (pin "2") (pinfunction "N/C_2") (pintype "passive"))
    )
    (net (code "90") (name "unconnected-(U6-N{slash}C-Pad9)") (class "Default")
      (node (ref "U6") (pin "9") (pinfunction "N/C_9") (pintype "passive"))
    )
    (net (code "91") (name "unconnected-(U6-N{slash}C-Pad12)") (class "Default")
      (node (ref "U6") (pin "12") (pinfunction "N/C_12") (pintype "passive"))
    )
    (net (code "92") (name "unconnected-(U6-N{slash}C-Pad13)") (class "Default")
      (node (ref "U6") (pin "13") (pinfunction "N/C_13") (pintype "passive"))
    )
    (net (code "93") (name "unconnected-(U6-N{slash}C-Pad14)") (class "Default")
      (node (ref "U6") (pin "14") (pinfunction "N/C_14") (pintype "passive"))
    )
    (net (code "94") (name "unconnected-(U6-N{slash}C-Pad16)") (class "Default")
      (node (ref "U6") (pin "16") (pinfunction "N/C_16") (pintype "passive"))
    )
    (net (code "95") (name "unconnected-(U6-_N{slash}C-Pad15)") (class "Default")
      (node (ref "U6") (pin "15") (pinfunction "_N/C_15") (pintype "passive"))
    )
  )
)
